# Esquematico.net
KiCad netlist of a schematic drawn in Altium Designer
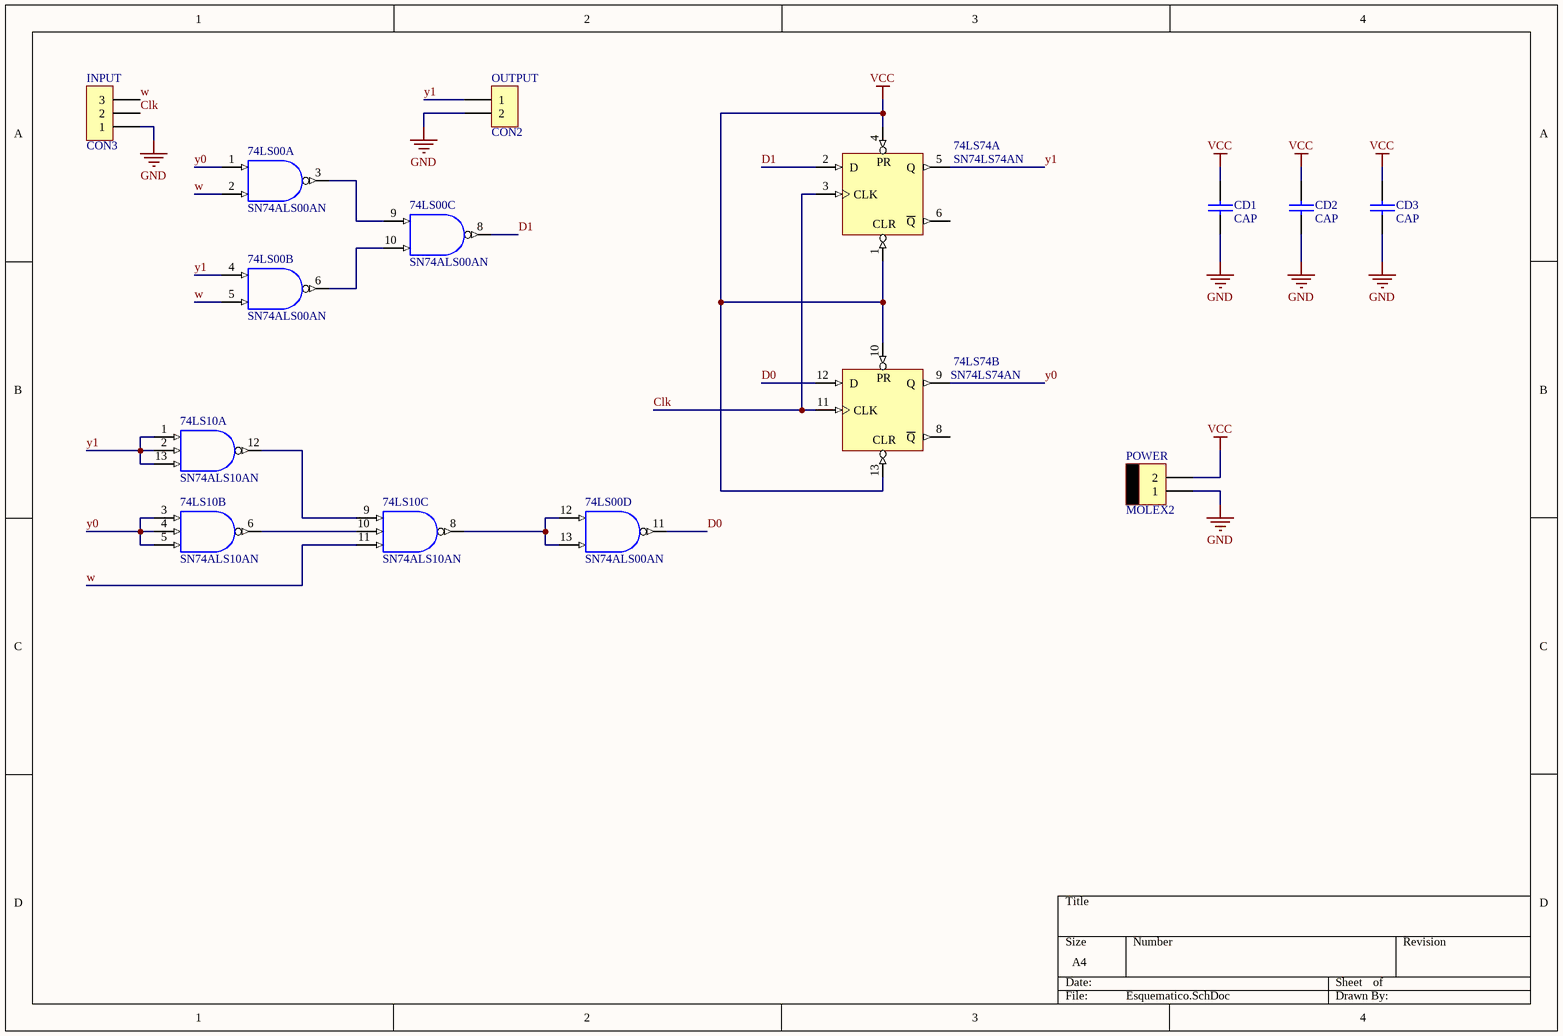
[diagram p0: Esquematico.SchDoc]

(export (version "E")
  (design (tool "Eeschema 10.0.6"))
  (components
    (comp (ref "74LS00")
      (value "SN74ALS00AN")
      (footprint "N014")
      (description "Quadruple 2-Input Positive-NAND Gate")
      (fields (field (name "PUBLISHER") "Altium Limited"))
      (libsource (lib "TI Logic Gate 1") (part "SN74ALS00AN"))
    )
    (comp (ref "74LS10")
      (value "SN74ALS10AN")
      (footprint "N014")
      (description "Triple 3-Input Positive-NAND Gate")
      (fields (field (name "PUBLISHER") "Altium Limited"))
      (libsource (lib "TI Logic Gate 1") (part "SN74ALS10AN"))
    )
    (comp (ref "74LS74")
      (value "SN74LS74AN")
      (footprint "N014D")
      (description "Dual D-Type Positive-Edge-Triggered Flip-Flop with Preset and Clear")
      (fields (field (name "PUBLISHER") "Altium Limited"))
      (libsource (lib "TI Logic Flip-Flop") (part "SN74LS74AN"))
    )
    (comp (ref "CD1") (value "CAP") (footprint "CAP200") (libsource (lib "LIBEBAL") (part "CAP")))
    (comp (ref "CD2") (value "CAP") (footprint "CAP200") (libsource (lib "LIBEBAL") (part "CAP")))
    (comp (ref "CD3") (value "CAP") (footprint "CAP200") (libsource (lib "LIBEBAL") (part "CAP")))
    (comp (ref "INPUT") (value "CON3") (footprint "SIP3") (libsource (lib "LIBEBAL") (part "CON3")))
    (comp (ref "OUTPUT") (value "CON2") (footprint "SIP2") (libsource (lib "LIBEBAL") (part "CON2")))
    (comp (ref "POWER") (value "MOLEX2") (footprint "MOLEX2") (libsource (lib "LIBEBAL") (part "MOLEX2")))
  )
  (nets
    (net (code "1") (name "/Clk") (class "Default")
      (node (ref "74LS74") (pin "11") (pinfunction "CLK_11") (pintype "input"))
      (node (ref "74LS74") (pin "3") (pinfunction "CLK_3") (pintype "input"))
      (node (ref "INPUT") (pin "2") (pinfunction "2_2") (pintype "passive"))
    )
    (net (code "2") (name "/D0") (class "Default")
      (node (ref "74LS00") (pin "11") (pinfunction "Y_11") (pintype "output"))
      (node (ref "74LS74") (pin "12") (pinfunction "D_12") (pintype "input"))
    )
    (net (code "3") (name "/D1") (class "Default")
      (node (ref "74LS00") (pin "8") (pinfunction "Y_8") (pintype "output"))
      (node (ref "74LS74") (pin "2") (pinfunction "D_2") (pintype "input"))
    )
    (net (code "4") (name "/w") (class "Default")
      (node (ref "74LS00") (pin "2") (pinfunction "B_2") (pintype "input"))
      (node (ref "74LS00") (pin "5") (pinfunction "B_5") (pintype "input"))
      (node (ref "74LS10") (pin "11") (pinfunction "C_11") (pintype "input"))
      (node (ref "INPUT") (pin "3") (pinfunction "3_3") (pintype "passive"))
    )
    (net (code "5") (name "/y0") (class "Default")
      (node (ref "74LS00") (pin "1") (pinfunction "A_1") (pintype "input"))
      (node (ref "74LS10") (pin "3") (pinfunction "A_3") (pintype "input"))
      (node (ref "74LS10") (pin "4") (pinfunction "B_4") (pintype "input"))
      (node (ref "74LS10") (pin "5") (pinfunction "C_5") (pintype "input"))
      (node (ref "74LS74") (pin "9") (pinfunction "Q_9") (pintype "output"))
    )
    (net (code "6") (name "/y1") (class "Default")
      (node (ref "74LS00") (pin "4") (pinfunction "A_4") (pintype "input"))
      (node (ref "74LS10") (pin "1") (pinfunction "A_1") (pintype "input"))
      (node (ref "74LS10") (pin "13") (pinfunction "C_13") (pintype "input"))
      (node (ref "74LS10") (pin "2") (pinfunction "B_2") (pintype "input"))
      (node (ref "74LS74") (pin "5") (pinfunction "Q_5") (pintype "output"))
      (node (ref "OUTPUT") (pin "1") (pinfunction "1_1") (pintype "passive"))
    )
    (net (code "7") (name "GND") (class "Default")
      (node (ref "74LS00") (pin "7") (pinfunction "GND_7") (pintype "power_in"))
      (node (ref "74LS10") (pin "7") (pinfunction "GND_7") (pintype "power_in"))
      (node (ref "74LS74") (pin "7") (pinfunction "GND_7") (pintype "power_in"))
      (node (ref "CD1") (pin "1") (pinfunction "1_1") (pintype "passive"))
      (node (ref "CD2") (pin "1") (pinfunction "1_1") (pintype "passive"))
      (node (ref "CD3") (pin "1") (pinfunction "1_1") (pintype "passive"))
      (node (ref "INPUT") (pin "1") (pinfunction "1_1") (pintype "passive"))
      (node (ref "OUTPUT") (pin "2") (pinfunction "2_2") (pintype "passive"))
      (node (ref "POWER") (pin "1") (pinfunction "1_1") (pintype "passive"))
    )
    (net (code "8") (name "Net-(74LS00A-Y)") (class "Default")
      (node (ref "74LS00") (pin "3") (pinfunction "Y_3") (pintype "output"))
      (node (ref "74LS00") (pin "9") (pinfunction "A_9") (pintype "input"))
    )
    (net (code "9") (name "Net-(74LS00B-Y)") (class "Default")
      (node (ref "74LS00") (pin "10") (pinfunction "B_10") (pintype "input"))
      (node (ref "74LS00") (pin "6") (pinfunction "Y_6") (pintype "output"))
    )
    (net (code "10") (name "Net-(74LS00D-A)") (class "Default")
      (node (ref "74LS00") (pin "12") (pinfunction "A_12") (pintype "input"))
      (node (ref "74LS00") (pin "13") (pinfunction "B_13") (pintype "input"))
      (node (ref "74LS10") (pin "8") (pinfunction "Y_8") (pintype "output"))
    )
    (net (code "11") (name "Net-(74LS10A-Y)") (class "Default")
      (node (ref "74LS10") (pin "12") (pinfunction "Y_12") (pintype "output"))
      (node (ref "74LS10") (pin "9") (pinfunction "A_9") (pintype "input"))
    )
    (net (code "12") (name "Net-(74LS10B-Y)") (class "Default")
      (node (ref "74LS10") (pin "10") (pinfunction "B_10") (pintype "input"))
      (node (ref "74LS10") (pin "6") (pinfunction "Y_6") (pintype "output"))
    )
    (net (code "13") (name "VCC") (class "Default")
      (node (ref "74LS00") (pin "14") (pinfunction "VCC_14") (pintype "power_in"))
      (node (ref "74LS10") (pin "14") (pinfunction "VCC_14") (pintype "power_in"))
      (node (ref "74LS74") (pin "1") (pinfunction "CLR_1") (pintype "input"))
      (node (ref "74LS74") (pin "10") (pinfunction "PR_10") (pintype "input"))
      (node (ref "74LS74") (pin "13") (pinfunction "CLR_13") (pintype "input"))
      (node (ref "74LS74") (pin "14") (pinfunction "VCC_14") (pintype "power_in"))
      (node (ref "74LS74") (pin "4") (pinfunction "PR_4") (pintype "input"))
      (node (ref "CD1") (pin "2") (pinfunction "2_2") (pintype "passive"))
      (node (ref "CD2") (pin "2") (pinfunction "2_2") (pintype "passive"))
      (node (ref "CD3") (pin "2") (pinfunction "2_2") (pintype "passive"))
      (node (ref "POWER") (pin "2") (pinfunction "2_2") (pintype "passive"))
    )
    (net (code "14") (name "unconnected-(74LS74A-~{Q}-Pad6)") (class "Default")
      (node (ref "74LS74") (pin "6") (pinfunction "~{Q}_6") (pintype "output"))
    )
    (net (code "15") (name "unconnected-(74LS74B-~{Q}-Pad8)") (class "Default")
      (node (ref "74LS74") (pin "8") (pinfunction "~{Q}_8") (pintype "output"))
    )
  )
)
